# 5V_AC-DC_REGULATOR.net
KiCad netlist of a schematic drawn in EAGLE
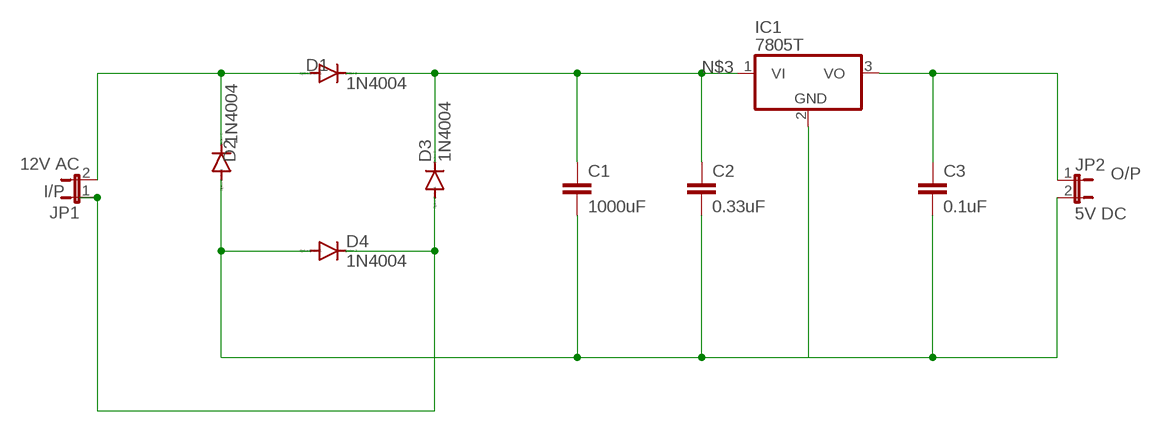
[diagram p0: schematic, sheet 1]

(export (version "E")
  (design (tool "Eeschema 10.0.6"))
  (components
    (comp (ref "C1")
      (value "1000uF")
      (footprint "eagle-import:C2.5-3")
      (libsource (lib "eagle-import") (part "C2,5-3"))
    )
    (comp (ref "C2")
      (value "0.33uF")
      (footprint "eagle-import:C2.5-3")
      (libsource (lib "eagle-import") (part "C2,5-3"))
    )
    (comp (ref "C3")
      (value "0.1uF")
      (footprint "eagle-import:C2.5-3")
      (libsource (lib "eagle-import") (part "C2,5-3"))
    )
    (comp (ref "D1")
      (value "1N4004")
      (footprint "eagle-import:DO41-10")
      (libsource (lib "eagle-import") (part "1N4004"))
    )
    (comp (ref "D2")
      (value "1N4004")
      (footprint "eagle-import:DO41-10")
      (libsource (lib "eagle-import") (part "1N4004"))
    )
    (comp (ref "D3")
      (value "1N4004")
      (footprint "eagle-import:DO41-10")
      (libsource (lib "eagle-import") (part "1N4004"))
    )
    (comp (ref "D4")
      (value "1N4004")
      (footprint "eagle-import:DO41-10")
      (libsource (lib "eagle-import") (part "1N4004"))
    )
    (comp (ref "IC1")
      (value "7805T")
      (footprint "eagle-import:TO220H")
      (libsource (lib "eagle-import") (part "78T05"))
    )
    (comp (ref "JP1")
      (value "12V AC")
      (footprint "eagle-import:JP1")
      (libsource (lib "eagle-import") (part "JP1E"))
    )
    (comp (ref "JP2")
      (value "5V DC")
      (footprint "eagle-import:JP1")
      (libsource (lib "eagle-import") (part "JP1E"))
    )
  )
  (nets
    (net (code "1") (name "/I{slash}P") (class "Default")
      (node (ref "D3") (pin "A") (pinfunction "A_A") (pintype "passive"))
      (node (ref "D4") (pin "C") (pinfunction "C_C") (pintype "passive"))
      (node (ref "JP1") (pin "1") (pinfunction "1_1") (pintype "passive"))
    )
    (net (code "2") (name "/N$3") (class "Default")
      (node (ref "C1") (pin "1") (pinfunction "1_1") (pintype "passive"))
      (node (ref "C2") (pin "1") (pinfunction "1_1") (pintype "passive"))
      (node (ref "D1") (pin "C") (pinfunction "C_C") (pintype "passive"))
      (node (ref "D3") (pin "C") (pinfunction "C_C") (pintype "passive"))
      (node (ref "IC1") (pin "1") (pinfunction "VI_1") (pintype "input"))
    )
    (net (code "3") (name "/O{slash}P") (class "Default")
      (node (ref "C3") (pin "1") (pinfunction "1_1") (pintype "passive"))
      (node (ref "IC1") (pin "3") (pinfunction "VO_3") (pintype "passive"))
      (node (ref "JP2") (pin "1") (pinfunction "1_1") (pintype "passive"))
    )
    (net (code "4") (name "Net-(D1-PadA)") (class "Default")
      (node (ref "D1") (pin "A") (pinfunction "A_A") (pintype "passive"))
      (node (ref "D2") (pin "C") (pinfunction "C_C") (pintype "passive"))
      (node (ref "JP1") (pin "2") (pinfunction "2_2") (pintype "passive"))
    )
    (net (code "5") (name "Net-(IC1-GND)") (class "Default")
      (node (ref "C1") (pin "2") (pinfunction "2_2") (pintype "passive"))
      (node (ref "C2") (pin "2") (pinfunction "2_2") (pintype "passive"))
      (node (ref "C3") (pin "2") (pinfunction "2_2") (pintype "passive"))
      (node (ref "D2") (pin "A") (pinfunction "A_A") (pintype "passive"))
      (node (ref "D4") (pin "A") (pinfunction "A_A") (pintype "passive"))
      (node (ref "IC1") (pin "2") (pinfunction "GND_2") (pintype "passive"))
      (node (ref "JP2") (pin "2") (pinfunction "2_2") (pintype "passive"))
    )
  )
)
